# ABFPanelV1.net
KiCad netlist of a schematic drawn in EAGLE
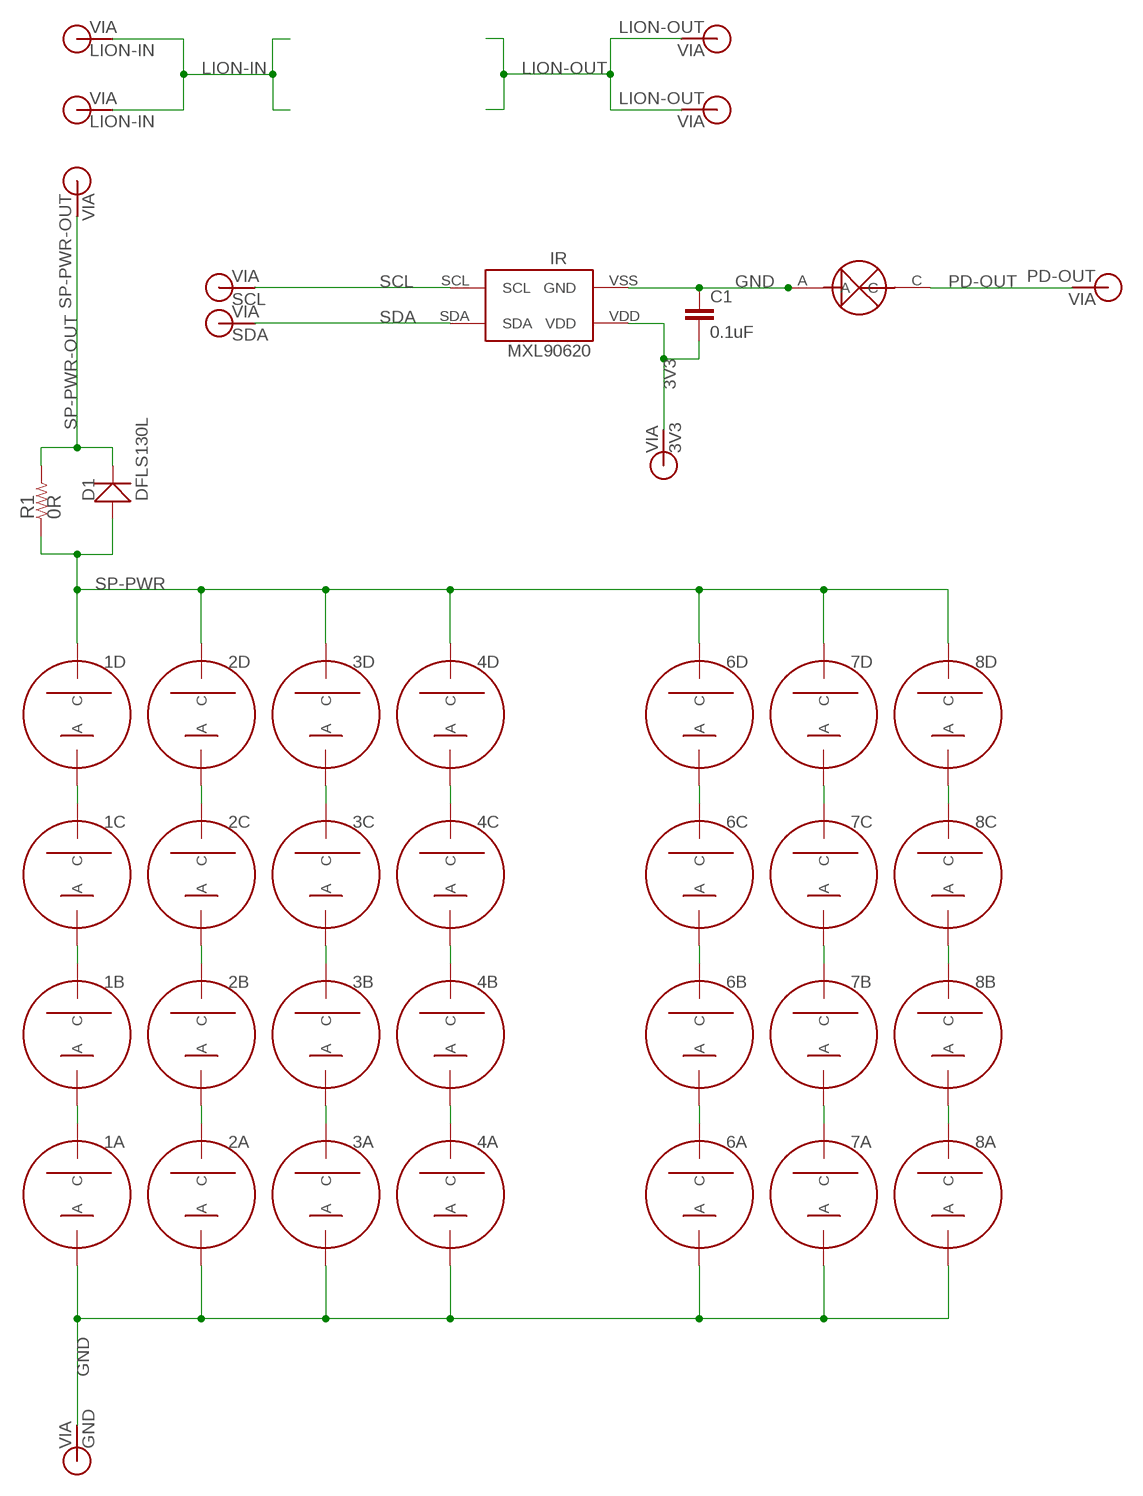
[diagram p0: schematic, sheet 1]

(export (version "E")
  (design (tool "Eeschema 10.0.6"))
  (components
    (comp (ref "1A")
      (value "SOLARCELLV3")
      (footprint "eagle-import:TRISOLX-V3")
      (libsource (lib "eagle-import") (part "SOLARCELLV3"))
    )
    (comp (ref "1B")
      (value "SOLARCELLV3")
      (footprint "eagle-import:TRISOLX-V3")
      (libsource (lib "eagle-import") (part "SOLARCELLV3"))
    )
    (comp (ref "1C")
      (value "SOLARCELLV3")
      (footprint "eagle-import:TRISOLX-V3")
      (libsource (lib "eagle-import") (part "SOLARCELLV3"))
    )
    (comp (ref "1D")
      (value "SOLARCELLV3")
      (footprint "eagle-import:TRISOLX-V3")
      (libsource (lib "eagle-import") (part "SOLARCELLV3"))
    )
    (comp (ref "2A")
      (value "SOLARCELLV3")
      (footprint "eagle-import:TRISOLX-V3")
      (libsource (lib "eagle-import") (part "SOLARCELLV3"))
    )
    (comp (ref "2B")
      (value "SOLARCELLV3")
      (footprint "eagle-import:TRISOLX-V3")
      (libsource (lib "eagle-import") (part "SOLARCELLV3"))
    )
    (comp (ref "2C")
      (value "SOLARCELLV3")
      (footprint "eagle-import:TRISOLX-V3")
      (libsource (lib "eagle-import") (part "SOLARCELLV3"))
    )
    (comp (ref "2D")
      (value "SOLARCELLV3")
      (footprint "eagle-import:TRISOLX-V3")
      (libsource (lib "eagle-import") (part "SOLARCELLV3"))
    )
    (comp (ref "3A")
      (value "SOLARCELLV3")
      (footprint "eagle-import:TRISOLX-V3")
      (libsource (lib "eagle-import") (part "SOLARCELLV3"))
    )
    (comp (ref "3B")
      (value "SOLARCELLV3")
      (footprint "eagle-import:TRISOLX-V3")
      (libsource (lib "eagle-import") (part "SOLARCELLV3"))
    )
    (comp (ref "3C")
      (value "SOLARCELLV3")
      (footprint "eagle-import:TRISOLX-V3")
      (libsource (lib "eagle-import") (part "SOLARCELLV3"))
    )
    (comp (ref "3D")
      (value "SOLARCELLV3")
      (footprint "eagle-import:TRISOLX-V3")
      (libsource (lib "eagle-import") (part "SOLARCELLV3"))
    )
    (comp (ref "3V3")
      (value "3V3")
      (footprint "eagle-import:VIA-60MIL")
      (libsource (lib "eagle-import") (part "VIA-60MIL"))
    )
    (comp (ref "4A")
      (value "SOLARCELLV3")
      (footprint "eagle-import:TRISOLX-V3")
      (libsource (lib "eagle-import") (part "SOLARCELLV3"))
    )
    (comp (ref "4B")
      (value "SOLARCELLV3")
      (footprint "eagle-import:TRISOLX-V3")
      (libsource (lib "eagle-import") (part "SOLARCELLV3"))
    )
    (comp (ref "4C")
      (value "SOLARCELLV3")
      (footprint "eagle-import:TRISOLX-V3")
      (libsource (lib "eagle-import") (part "SOLARCELLV3"))
    )
    (comp (ref "4D")
      (value "SOLARCELLV3")
      (footprint "eagle-import:TRISOLX-V3")
      (libsource (lib "eagle-import") (part "SOLARCELLV3"))
    )
    (comp (ref "6A")
      (value "SOLARCELLV3")
      (footprint "eagle-import:TRISOLX-V3")
      (libsource (lib "eagle-import") (part "SOLARCELLV3"))
    )
    (comp (ref "6B")
      (value "SOLARCELLV3")
      (footprint "eagle-import:TRISOLX-V3")
      (libsource (lib "eagle-import") (part "SOLARCELLV3"))
    )
    (comp (ref "6C")
      (value "SOLARCELLV3")
      (footprint "eagle-import:TRISOLX-V3")
      (libsource (lib "eagle-import") (part "SOLARCELLV3"))
    )
    (comp (ref "6D")
      (value "SOLARCELLV3")
      (footprint "eagle-import:TRISOLX-V3")
      (libsource (lib "eagle-import") (part "SOLARCELLV3"))
    )
    (comp (ref "7A")
      (value "SOLARCELLV3")
      (footprint "eagle-import:TRISOLX-V3")
      (libsource (lib "eagle-import") (part "SOLARCELLV3"))
    )
    (comp (ref "7B")
      (value "SOLARCELLV3")
      (footprint "eagle-import:TRISOLX-V3")
      (libsource (lib "eagle-import") (part "SOLARCELLV3"))
    )
    (comp (ref "7C")
      (value "SOLARCELLV3")
      (footprint "eagle-import:TRISOLX-V3")
      (libsource (lib "eagle-import") (part "SOLARCELLV3"))
    )
    (comp (ref "7D")
      (value "SOLARCELLV3")
      (footprint "eagle-import:TRISOLX-V3")
      (libsource (lib "eagle-import") (part "SOLARCELLV3"))
    )
    (comp (ref "8A")
      (value "SOLARCELLV3")
      (footprint "eagle-import:TRISOLX-V3")
      (libsource (lib "eagle-import") (part "SOLARCELLV3"))
    )
    (comp (ref "8B")
      (value "SOLARCELLV3")
      (footprint "eagle-import:TRISOLX-V3")
      (libsource (lib "eagle-import") (part "SOLARCELLV3"))
    )
    (comp (ref "8C")
      (value "SOLARCELLV3")
      (footprint "eagle-import:TRISOLX-V3")
      (libsource (lib "eagle-import") (part "SOLARCELLV3"))
    )
    (comp (ref "8D")
      (value "SOLARCELLV3")
      (footprint "eagle-import:TRISOLX-V3")
      (libsource (lib "eagle-import") (part "SOLARCELLV3"))
    )
    (comp (ref "C1")
      (value "0.1uF")
      (footprint "eagle-import:0805")
      (libsource (lib "eagle-import") (part "CAP0805"))
    )
    (comp (ref "D1")
      (value "DFLS130L")
      (footprint "eagle-import:PWRDI-123")
      (libsource (lib "eagle-import") (part "DFLS130L"))
    )
    (comp (ref "GND")
      (value "GND")
      (footprint "eagle-import:VIA-60MIL")
      (libsource (lib "eagle-import") (part "VIA-60MIL"))
    )
    (comp (ref "IR")
      (value "MXL90620")
      (footprint "eagle-import:MXL90620")
      (libsource (lib "eagle-import") (part "MXL90620"))
    )
    (comp (ref "PD")
      (value "PHOTODETECTOR")
      (footprint "eagle-import:PHOTODECTORDEVICE2")
      (libsource (lib "eagle-import") (part "PHOTODETECTOR"))
    )
    (comp (ref "PD-OUT")
      (value "PD-OUT")
      (footprint "eagle-import:VIA-60MIL")
      (libsource (lib "eagle-import") (part "VIA-60MIL"))
    )
    (comp (ref "PWR-OUT")
      (value "SP-PWR-OUT")
      (footprint "eagle-import:VIA-60MIL")
      (libsource (lib "eagle-import") (part "VIA-60MIL"))
    )
    (comp (ref "R1")
      (value "0R")
      (footprint "eagle-import:1210")
      (libsource (lib "eagle-import") (part "RES1210"))
    )
    (comp (ref "SCL")
      (value "SCL")
      (footprint "eagle-import:VIA-60MIL")
      (libsource (lib "eagle-import") (part "VIA-60MIL"))
    )
    (comp (ref "SDA")
      (value "SDA")
      (footprint "eagle-import:VIA-60MIL")
      (libsource (lib "eagle-import") (part "VIA-60MIL"))
    )
    (comp (ref "V1")
      (value "LION-IN")
      (footprint "eagle-import:VIA-60MIL")
      (libsource (lib "eagle-import") (part "VIA-60MIL"))
    )
    (comp (ref "V2")
      (value "LION-IN")
      (footprint "eagle-import:VIA-60MIL")
      (libsource (lib "eagle-import") (part "VIA-60MIL"))
    )
    (comp (ref "V3")
      (value "LION-OUT")
      (footprint "eagle-import:VIA-60MIL")
      (libsource (lib "eagle-import") (part "VIA-60MIL"))
    )
    (comp (ref "V4")
      (value "LION-OUT")
      (footprint "eagle-import:VIA-60MIL")
      (libsource (lib "eagle-import") (part "VIA-60MIL"))
    )
  )
  (nets
    (net (code "1") (name "/3V3") (class "Default")
      (node (ref "3V3") (pin "P$1") (pinfunction "P$1_P$1") (pintype "bidirectional"))
      (node (ref "C1") (pin "2") (pinfunction "2_2") (pintype "passive"))
      (node (ref "IR") (pin "VDD") (pinfunction "VDD_VDD") (pintype "bidirectional"))
    )
    (net (code "2") (name "/GND") (class "Default")
      (node (ref "1A") (pin "ANODE") (pinfunction "A_ANODE") (pintype "bidirectional"))
      (node (ref "2A") (pin "ANODE") (pinfunction "A_ANODE") (pintype "bidirectional"))
      (node (ref "3A") (pin "ANODE") (pinfunction "A_ANODE") (pintype "bidirectional"))
      (node (ref "4A") (pin "ANODE") (pinfunction "A_ANODE") (pintype "bidirectional"))
      (node (ref "6A") (pin "ANODE") (pinfunction "A_ANODE") (pintype "bidirectional"))
      (node (ref "7A") (pin "ANODE") (pinfunction "A_ANODE") (pintype "bidirectional"))
      (node (ref "8A") (pin "ANODE") (pinfunction "A_ANODE") (pintype "bidirectional"))
      (node (ref "C1") (pin "1") (pinfunction "1_1") (pintype "passive"))
      (node (ref "GND") (pin "P$1") (pinfunction "P$1_P$1") (pintype "bidirectional"))
      (node (ref "IR") (pin "VSS") (pinfunction "GND_VSS") (pintype "bidirectional"))
      (node (ref "PD") (pin "A") (pinfunction "A_A") (pintype "bidirectional"))
    )
    (net (code "3") (name "/LION-IN") (class "Default")
      (node (ref "V1") (pin "P$1") (pinfunction "P$1_P$1") (pintype "bidirectional"))
      (node (ref "V2") (pin "P$1") (pinfunction "P$1_P$1") (pintype "bidirectional"))
    )
    (net (code "4") (name "/LION-OUT") (class "Default")
      (node (ref "V3") (pin "P$1") (pinfunction "P$1_P$1") (pintype "bidirectional"))
      (node (ref "V4") (pin "P$1") (pinfunction "P$1_P$1") (pintype "bidirectional"))
    )
    (net (code "5") (name "/PD-OUT") (class "Default")
      (node (ref "PD") (pin "C") (pinfunction "C_C") (pintype "bidirectional"))
      (node (ref "PD-OUT") (pin "P$1") (pinfunction "P$1_P$1") (pintype "bidirectional"))
    )
    (net (code "6") (name "/SCL") (class "Default")
      (node (ref "IR") (pin "SCL") (pinfunction "SCL_SCL") (pintype "bidirectional"))
      (node (ref "SCL") (pin "P$1") (pinfunction "P$1_P$1") (pintype "bidirectional"))
    )
    (net (code "7") (name "/SDA") (class "Default")
      (node (ref "IR") (pin "SDA") (pinfunction "SDA_SDA") (pintype "bidirectional"))
      (node (ref "SDA") (pin "P$1") (pinfunction "P$1_P$1") (pintype "bidirectional"))
    )
    (net (code "8") (name "/SP-PWR") (class "Default")
      (node (ref "1D") (pin "CATHODE") (pinfunction "C_CATHODE") (pintype "bidirectional"))
      (node (ref "2D") (pin "CATHODE") (pinfunction "C_CATHODE") (pintype "bidirectional"))
      (node (ref "3D") (pin "CATHODE") (pinfunction "C_CATHODE") (pintype "bidirectional"))
      (node (ref "4D") (pin "CATHODE") (pinfunction "C_CATHODE") (pintype "bidirectional"))
      (node (ref "6D") (pin "CATHODE") (pinfunction "C_CATHODE") (pintype "bidirectional"))
      (node (ref "7D") (pin "CATHODE") (pinfunction "C_CATHODE") (pintype "bidirectional"))
      (node (ref "8D") (pin "CATHODE") (pinfunction "C_CATHODE") (pintype "bidirectional"))
      (node (ref "D1") (pin "A") (pinfunction "A_A") (pintype "bidirectional"))
      (node (ref "R1") (pin "P$1") (pinfunction "1_P$1") (pintype "passive"))
    )
    (net (code "9") (name "/SP-PWR-OUT") (class "Default")
      (node (ref "D1") (pin "C") (pinfunction "C_C") (pintype "bidirectional"))
      (node (ref "PWR-OUT") (pin "P$1") (pinfunction "P$1_P$1") (pintype "bidirectional"))
      (node (ref "R1") (pin "P$2") (pinfunction "2_P$2") (pintype "passive"))
    )
    (net (code "10") (name "Net-(1A-C)") (class "Default")
      (node (ref "1A") (pin "CATHODE") (pinfunction "C_CATHODE") (pintype "bidirectional"))
      (node (ref "1B") (pin "ANODE") (pinfunction "A_ANODE") (pintype "bidirectional"))
    )
    (net (code "11") (name "Net-(1B-C)") (class "Default")
      (node (ref "1B") (pin "CATHODE") (pinfunction "C_CATHODE") (pintype "bidirectional"))
      (node (ref "1C") (pin "ANODE") (pinfunction "A_ANODE") (pintype "bidirectional"))
    )
    (net (code "12") (name "Net-(1C-C)") (class "Default")
      (node (ref "1C") (pin "CATHODE") (pinfunction "C_CATHODE") (pintype "bidirectional"))
      (node (ref "1D") (pin "ANODE") (pinfunction "A_ANODE") (pintype "bidirectional"))
    )
    (net (code "13") (name "Net-(2A-C)") (class "Default")
      (node (ref "2A") (pin "CATHODE") (pinfunction "C_CATHODE") (pintype "bidirectional"))
      (node (ref "2B") (pin "ANODE") (pinfunction "A_ANODE") (pintype "bidirectional"))
    )
    (net (code "14") (name "Net-(2B-C)") (class "Default")
      (node (ref "2B") (pin "CATHODE") (pinfunction "C_CATHODE") (pintype "bidirectional"))
      (node (ref "2C") (pin "ANODE") (pinfunction "A_ANODE") (pintype "bidirectional"))
    )
    (net (code "15") (name "Net-(2C-C)") (class "Default")
      (node (ref "2C") (pin "CATHODE") (pinfunction "C_CATHODE") (pintype "bidirectional"))
      (node (ref "2D") (pin "ANODE") (pinfunction "A_ANODE") (pintype "bidirectional"))
    )
    (net (code "16") (name "Net-(3A-C)") (class "Default")
      (node (ref "3A") (pin "CATHODE") (pinfunction "C_CATHODE") (pintype "bidirectional"))
      (node (ref "3B") (pin "ANODE") (pinfunction "A_ANODE") (pintype "bidirectional"))
    )
    (net (code "17") (name "Net-(3B-C)") (class "Default")
      (node (ref "3B") (pin "CATHODE") (pinfunction "C_CATHODE") (pintype "bidirectional"))
      (node (ref "3C") (pin "ANODE") (pinfunction "A_ANODE") (pintype "bidirectional"))
    )
    (net (code "18") (name "Net-(3C-C)") (class "Default")
      (node (ref "3C") (pin "CATHODE") (pinfunction "C_CATHODE") (pintype "bidirectional"))
      (node (ref "3D") (pin "ANODE") (pinfunction "A_ANODE") (pintype "bidirectional"))
    )
    (net (code "19") (name "Net-(4A-C)") (class "Default")
      (node (ref "4A") (pin "CATHODE") (pinfunction "C_CATHODE") (pintype "bidirectional"))
      (node (ref "4B") (pin "ANODE") (pinfunction "A_ANODE") (pintype "bidirectional"))
    )
    (net (code "20") (name "Net-(4B-C)") (class "Default")
      (node (ref "4B") (pin "CATHODE") (pinfunction "C_CATHODE") (pintype "bidirectional"))
      (node (ref "4C") (pin "ANODE") (pinfunction "A_ANODE") (pintype "bidirectional"))
    )
    (net (code "21") (name "Net-(4C-C)") (class "Default")
      (node (ref "4C") (pin "CATHODE") (pinfunction "C_CATHODE") (pintype "bidirectional"))
      (node (ref "4D") (pin "ANODE") (pinfunction "A_ANODE") (pintype "bidirectional"))
    )
    (net (code "22") (name "Net-(6A-C)") (class "Default")
      (node (ref "6A") (pin "CATHODE") (pinfunction "C_CATHODE") (pintype "bidirectional"))
      (node (ref "6B") (pin "ANODE") (pinfunction "A_ANODE") (pintype "bidirectional"))
    )
    (net (code "23") (name "Net-(6B-C)") (class "Default")
      (node (ref "6B") (pin "CATHODE") (pinfunction "C_CATHODE") (pintype "bidirectional"))
      (node (ref "6C") (pin "ANODE") (pinfunction "A_ANODE") (pintype "bidirectional"))
    )
    (net (code "24") (name "Net-(6C-C)") (class "Default")
      (node (ref "6C") (pin "CATHODE") (pinfunction "C_CATHODE") (pintype "bidirectional"))
      (node (ref "6D") (pin "ANODE") (pinfunction "A_ANODE") (pintype "bidirectional"))
    )
    (net (code "25") (name "Net-(7A-C)") (class "Default")
      (node (ref "7A") (pin "CATHODE") (pinfunction "C_CATHODE") (pintype "bidirectional"))
      (node (ref "7B") (pin "ANODE") (pinfunction "A_ANODE") (pintype "bidirectional"))
    )
    (net (code "26") (name "Net-(7B-C)") (class "Default")
      (node (ref "7B") (pin "CATHODE") (pinfunction "C_CATHODE") (pintype "bidirectional"))
      (node (ref "7C") (pin "ANODE") (pinfunction "A_ANODE") (pintype "bidirectional"))
    )
    (net (code "27") (name "Net-(7C-C)") (class "Default")
      (node (ref "7C") (pin "CATHODE") (pinfunction "C_CATHODE") (pintype "bidirectional"))
      (node (ref "7D") (pin "ANODE") (pinfunction "A_ANODE") (pintype "bidirectional"))
    )
    (net (code "28") (name "Net-(8A-C)") (class "Default")
      (node (ref "8A") (pin "CATHODE") (pinfunction "C_CATHODE") (pintype "bidirectional"))
      (node (ref "8B") (pin "ANODE") (pinfunction "A_ANODE") (pintype "bidirectional"))
    )
    (net (code "29") (name "Net-(8B-C)") (class "Default")
      (node (ref "8B") (pin "CATHODE") (pinfunction "C_CATHODE") (pintype "bidirectional"))
      (node (ref "8C") (pin "ANODE") (pinfunction "A_ANODE") (pintype "bidirectional"))
    )
    (net (code "30") (name "Net-(8C-C)") (class "Default")
      (node (ref "8C") (pin "CATHODE") (pinfunction "C_CATHODE") (pintype "bidirectional"))
      (node (ref "8D") (pin "ANODE") (pinfunction "A_ANODE") (pintype "bidirectional"))
    )
  )
)
